# stepprobetojtag.net
KiCad netlist of a schematic drawn in EasyEDA Pro
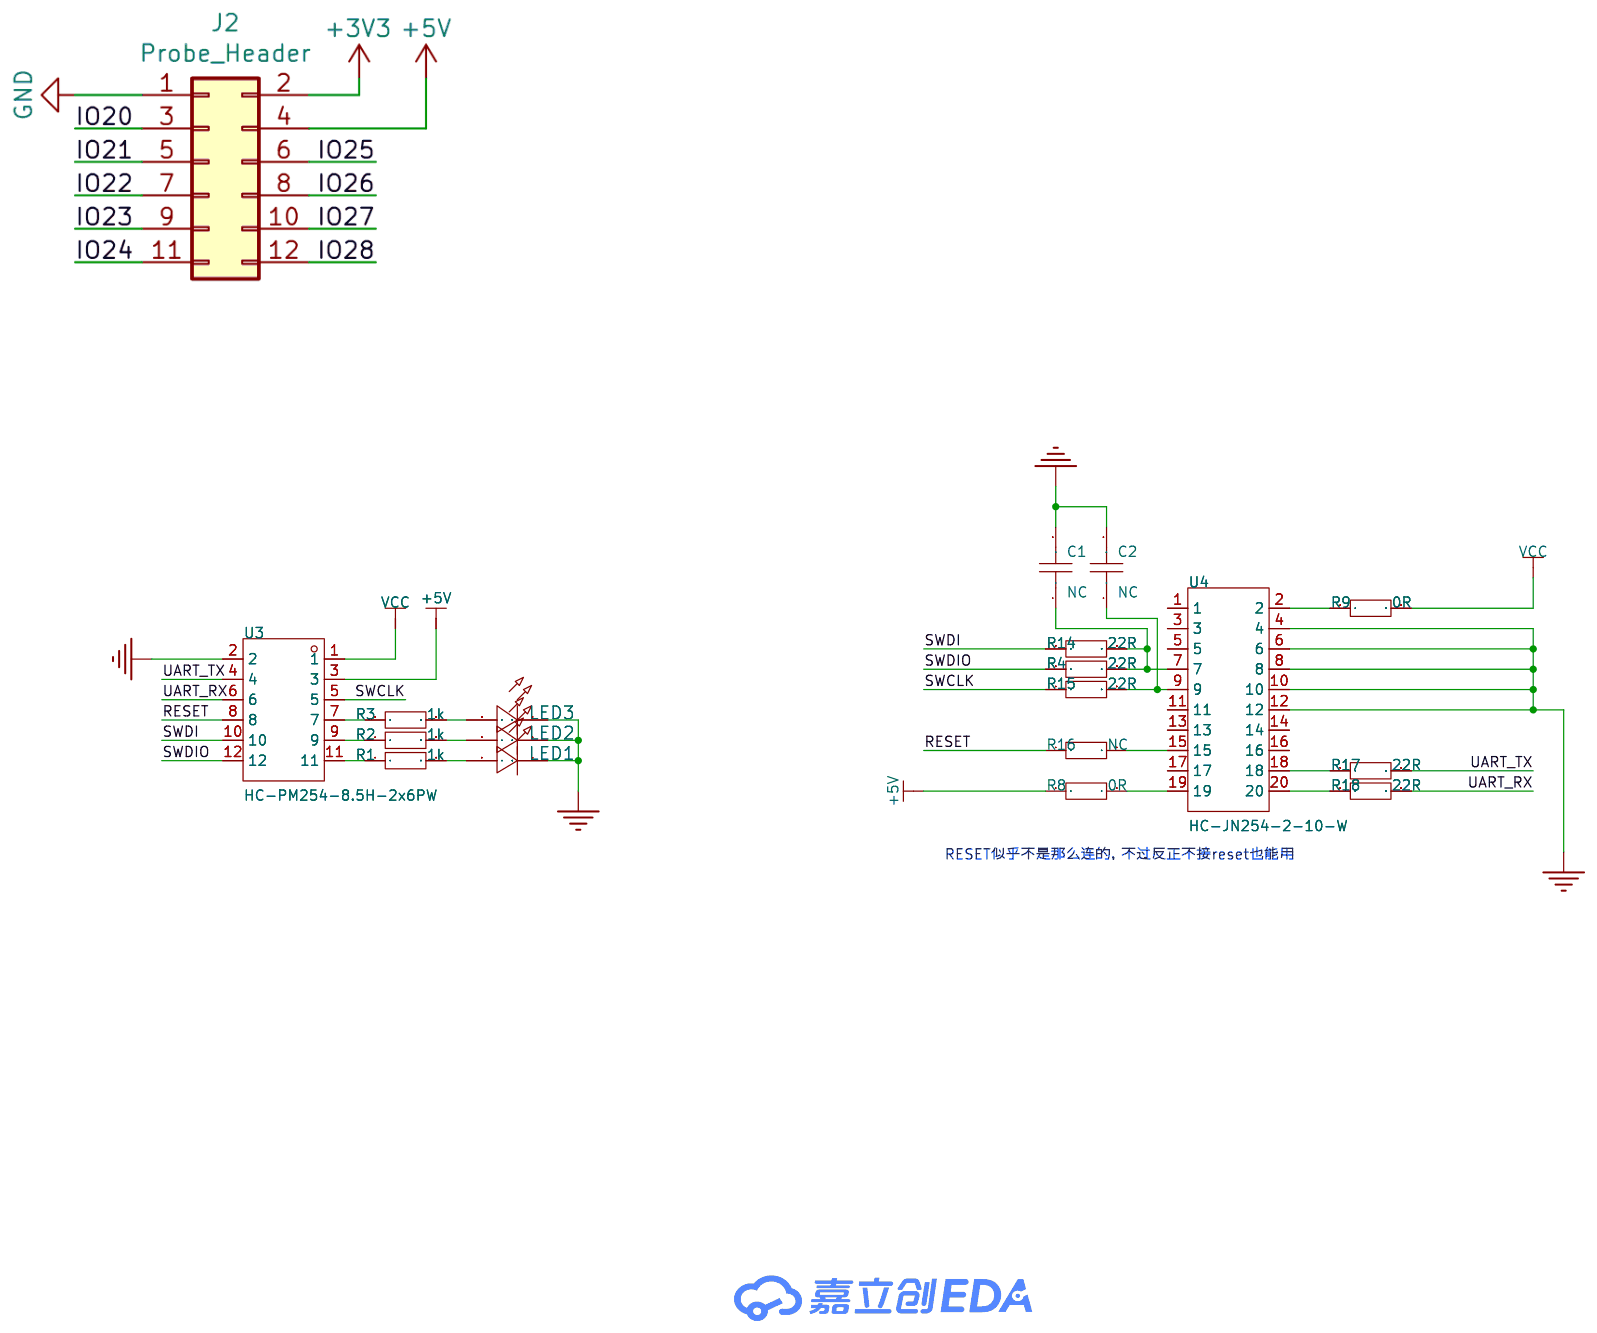
[diagram p0: schematic sheet]

(export (version "E")
  (design (tool "Eeschema 10.0.6"))
  (components
    (comp (ref "C1")
      (value "NC")
      (footprint "easyedapro:C0603")
      (libsource (lib "easyedapro") (part "CapAcitance"))
    )
    (comp (ref "C2")
      (value "NC")
      (footprint "easyedapro:C0603")
      (libsource (lib "easyedapro") (part "CapAcitance"))
    )
    (comp (ref "LED1")
      (value "~")
      (footprint "easyedapro:LED_0603")
      (libsource (lib "easyedapro") (part "LED_R"))
    )
    (comp (ref "LED2")
      (value "~")
      (footprint "easyedapro:LED_0603")
      (libsource (lib "easyedapro") (part "LED_R"))
    )
    (comp (ref "LED3")
      (value "~")
      (footprint "easyedapro:LED_0603")
      (libsource (lib "easyedapro") (part "LED_R"))
    )
    (comp (ref "R1") (value "1k") (footprint "easyedapro:R0603") (libsource (lib "easyedapro") (part "电阻")))
    (comp (ref "R2") (value "1k") (footprint "easyedapro:R0603") (libsource (lib "easyedapro") (part "电阻")))
    (comp (ref "R3") (value "1k") (footprint "easyedapro:R0603") (libsource (lib "easyedapro") (part "电阻")))
    (comp (ref "R4") (value "22R") (footprint "easyedapro:R0603") (libsource (lib "easyedapro") (part "电阻")))
    (comp (ref "R8") (value "0R") (footprint "easyedapro:R0603") (libsource (lib "easyedapro") (part "电阻")))
    (comp (ref "R9") (value "0R") (footprint "easyedapro:R0603") (libsource (lib "easyedapro") (part "电阻")))
    (comp (ref "R14") (value "22R") (footprint "easyedapro:R0603") (libsource (lib "easyedapro") (part "电阻")))
    (comp (ref "R15") (value "22R") (footprint "easyedapro:R0603") (libsource (lib "easyedapro") (part "电阻")))
    (comp (ref "R16") (value "NC") (footprint "easyedapro:R0603") (libsource (lib "easyedapro") (part "电阻")))
    (comp (ref "R17") (value "22R") (footprint "easyedapro:R0603") (libsource (lib "easyedapro") (part "电阻")))
    (comp (ref "R18") (value "22R") (footprint "easyedapro:R0603") (libsource (lib "easyedapro") (part "电阻")))
    (comp (ref "U3")
      (value "HC-PM254-8.5H-2x6PW")
      (footprint "easyedapro:CONN-TH_HC-PM254-8.5H-2X6PW")
      (fields (field (name "Manufacturer") "HC(虹成电子)"))
      (libsource (lib "easyedapro") (part "HC-PM254-8.5H-2X6PW"))
    )
    (comp (ref "U4")
      (value "HC-JN254-2-10-W")
      (footprint "easyedapro:HDR-TH_HC-JN254-2-10-W")
      (fields (field (name "Manufacturer") "HCTL(华灿天禄)"))
      (libsource (lib "easyedapro") (part "HC-JN254-2-10-W"))
    )
  )
  (nets
    (net (code "1") (name "+5V") (class "Default")
      (node (ref "R8") (pin "1") (pinfunction "1_1") (pintype "input"))
      (node (ref "U3") (pin "3") (pinfunction "3_3") (pintype "unspecified"))
    )
    (net (code "2") (name "/RESET") (class "Default")
      (node (ref "R16") (pin "1") (pinfunction "1_1") (pintype "input"))
      (node (ref "U3") (pin "8") (pinfunction "8_8") (pintype "unspecified"))
    )
    (net (code "3") (name "/SWCLK") (class "Default")
      (node (ref "R15") (pin "1") (pinfunction "1_1") (pintype "input"))
      (node (ref "U3") (pin "5") (pinfunction "5_5") (pintype "unspecified"))
    )
    (net (code "4") (name "/SWDI") (class "Default")
      (node (ref "R14") (pin "1") (pinfunction "1_1") (pintype "input"))
      (node (ref "U3") (pin "10") (pinfunction "10_10") (pintype "unspecified"))
    )
    (net (code "5") (name "/SWDIO") (class "Default")
      (node (ref "R4") (pin "1") (pinfunction "1_1") (pintype "input"))
      (node (ref "U3") (pin "12") (pinfunction "12_12") (pintype "unspecified"))
    )
    (net (code "6") (name "/UART_RX") (class "Default")
      (node (ref "R18") (pin "2") (pinfunction "2_2") (pintype "input"))
      (node (ref "U3") (pin "6") (pinfunction "6_6") (pintype "unspecified"))
    )
    (net (code "7") (name "/UART_TX") (class "Default")
      (node (ref "R17") (pin "2") (pinfunction "2_2") (pintype "input"))
      (node (ref "U3") (pin "4") (pinfunction "4_4") (pintype "unspecified"))
    )
    (net (code "8") (name "GND") (class "Default")
      (node (ref "C1") (pin "2") (pinfunction "2_2") (pintype "input"))
      (node (ref "C2") (pin "2") (pinfunction "2_2") (pintype "input"))
      (node (ref "LED1") (pin "1") (pinfunction "C_1") (pintype "input"))
      (node (ref "LED2") (pin "1") (pinfunction "C_1") (pintype "input"))
      (node (ref "LED3") (pin "1") (pinfunction "C_1") (pintype "input"))
      (node (ref "U3") (pin "2") (pinfunction "2_2") (pintype "unspecified"))
      (node (ref "U4") (pin "10") (pinfunction "10_10") (pintype "unspecified"))
      (node (ref "U4") (pin "12") (pinfunction "12_12") (pintype "unspecified"))
      (node (ref "U4") (pin "4") (pinfunction "4_4") (pintype "unspecified"))
      (node (ref "U4") (pin "6") (pinfunction "6_6") (pintype "unspecified"))
      (node (ref "U4") (pin "8") (pinfunction "8_8") (pintype "unspecified"))
    )
    (net (code "9") (name "Net-(C1-Pad1)") (class "Default")
      (node (ref "C1") (pin "1") (pinfunction "1_1") (pintype "input"))
      (node (ref "R14") (pin "2") (pinfunction "2_2") (pintype "input"))
      (node (ref "R4") (pin "2") (pinfunction "2_2") (pintype "input"))
      (node (ref "U4") (pin "7") (pinfunction "7_7") (pintype "unspecified"))
    )
    (net (code "10") (name "Net-(C2-Pad1)") (class "Default")
      (node (ref "C2") (pin "1") (pinfunction "1_1") (pintype "input"))
      (node (ref "R15") (pin "2") (pinfunction "2_2") (pintype "input"))
      (node (ref "U4") (pin "9") (pinfunction "9_9") (pintype "unspecified"))
    )
    (net (code "11") (name "Net-(LED1-A)") (class "Default")
      (node (ref "LED1") (pin "2") (pinfunction "A_2") (pintype "input"))
      (node (ref "R1") (pin "2") (pinfunction "2_2") (pintype "input"))
    )
    (net (code "12") (name "Net-(LED2-A)") (class "Default")
      (node (ref "LED2") (pin "2") (pinfunction "A_2") (pintype "input"))
      (node (ref "R2") (pin "2") (pinfunction "2_2") (pintype "input"))
    )
    (net (code "13") (name "Net-(LED3-A)") (class "Default")
      (node (ref "LED3") (pin "2") (pinfunction "A_2") (pintype "input"))
      (node (ref "R3") (pin "2") (pinfunction "2_2") (pintype "input"))
    )
    (net (code "14") (name "Net-(R1-Pad1)") (class "Default")
      (node (ref "R1") (pin "1") (pinfunction "1_1") (pintype "input"))
      (node (ref "U3") (pin "11") (pinfunction "11_11") (pintype "unspecified"))
    )
    (net (code "15") (name "Net-(R2-Pad1)") (class "Default")
      (node (ref "R2") (pin "1") (pinfunction "1_1") (pintype "input"))
      (node (ref "U3") (pin "9") (pinfunction "9_9") (pintype "unspecified"))
    )
    (net (code "16") (name "Net-(R3-Pad1)") (class "Default")
      (node (ref "R3") (pin "1") (pinfunction "1_1") (pintype "input"))
      (node (ref "U3") (pin "7") (pinfunction "7_7") (pintype "unspecified"))
    )
    (net (code "17") (name "Net-(R8-Pad2)") (class "Default")
      (node (ref "R8") (pin "2") (pinfunction "2_2") (pintype "input"))
      (node (ref "U4") (pin "19") (pinfunction "19_19") (pintype "unspecified"))
    )
    (net (code "18") (name "Net-(R9-Pad1)") (class "Default")
      (node (ref "R9") (pin "1") (pinfunction "1_1") (pintype "input"))
      (node (ref "U4") (pin "2") (pinfunction "2_2") (pintype "unspecified"))
    )
    (net (code "19") (name "Net-(R16-Pad2)") (class "Default")
      (node (ref "R16") (pin "2") (pinfunction "2_2") (pintype "input"))
      (node (ref "U4") (pin "15") (pinfunction "15_15") (pintype "unspecified"))
    )
    (net (code "20") (name "Net-(R17-Pad1)") (class "Default")
      (node (ref "R17") (pin "1") (pinfunction "1_1") (pintype "input"))
      (node (ref "U4") (pin "18") (pinfunction "18_18") (pintype "unspecified"))
    )
    (net (code "21") (name "Net-(R18-Pad1)") (class "Default")
      (node (ref "R18") (pin "1") (pinfunction "1_1") (pintype "input"))
      (node (ref "U4") (pin "20") (pinfunction "20_20") (pintype "unspecified"))
    )
    (net (code "22") (name "VCC") (class "Default")
      (node (ref "R9") (pin "2") (pinfunction "2_2") (pintype "input"))
      (node (ref "U3") (pin "1") (pinfunction "1_1") (pintype "unspecified"))
    )
    (net (code "23") (name "unconnected-(U4-Pad1)") (class "Default")
      (node (ref "U4") (pin "1") (pinfunction "1_1") (pintype "unspecified"))
    )
    (net (code "24") (name "unconnected-(U4-Pad3)") (class "Default")
      (node (ref "U4") (pin "3") (pinfunction "3_3") (pintype "unspecified"))
    )
    (net (code "25") (name "unconnected-(U4-Pad5)") (class "Default")
      (node (ref "U4") (pin "5") (pinfunction "5_5") (pintype "unspecified"))
    )
    (net (code "26") (name "unconnected-(U4-Pad11)") (class "Default")
      (node (ref "U4") (pin "11") (pinfunction "11_11") (pintype "unspecified"))
    )
    (net (code "27") (name "unconnected-(U4-Pad13)") (class "Default")
      (node (ref "U4") (pin "13") (pinfunction "13_13") (pintype "unspecified"))
    )
    (net (code "28") (name "unconnected-(U4-Pad14)") (class "Default")
      (node (ref "U4") (pin "14") (pinfunction "14_14") (pintype "unspecified"))
    )
    (net (code "29") (name "unconnected-(U4-Pad16)") (class "Default")
      (node (ref "U4") (pin "16") (pinfunction "16_16") (pintype "unspecified"))
    )
    (net (code "30") (name "unconnected-(U4-Pad17)") (class "Default")
      (node (ref "U4") (pin "17") (pinfunction "17_17") (pintype "unspecified"))
    )
  )
)
